# PowerSupply.net
KiCad netlist of a schematic drawn in Altium Designer
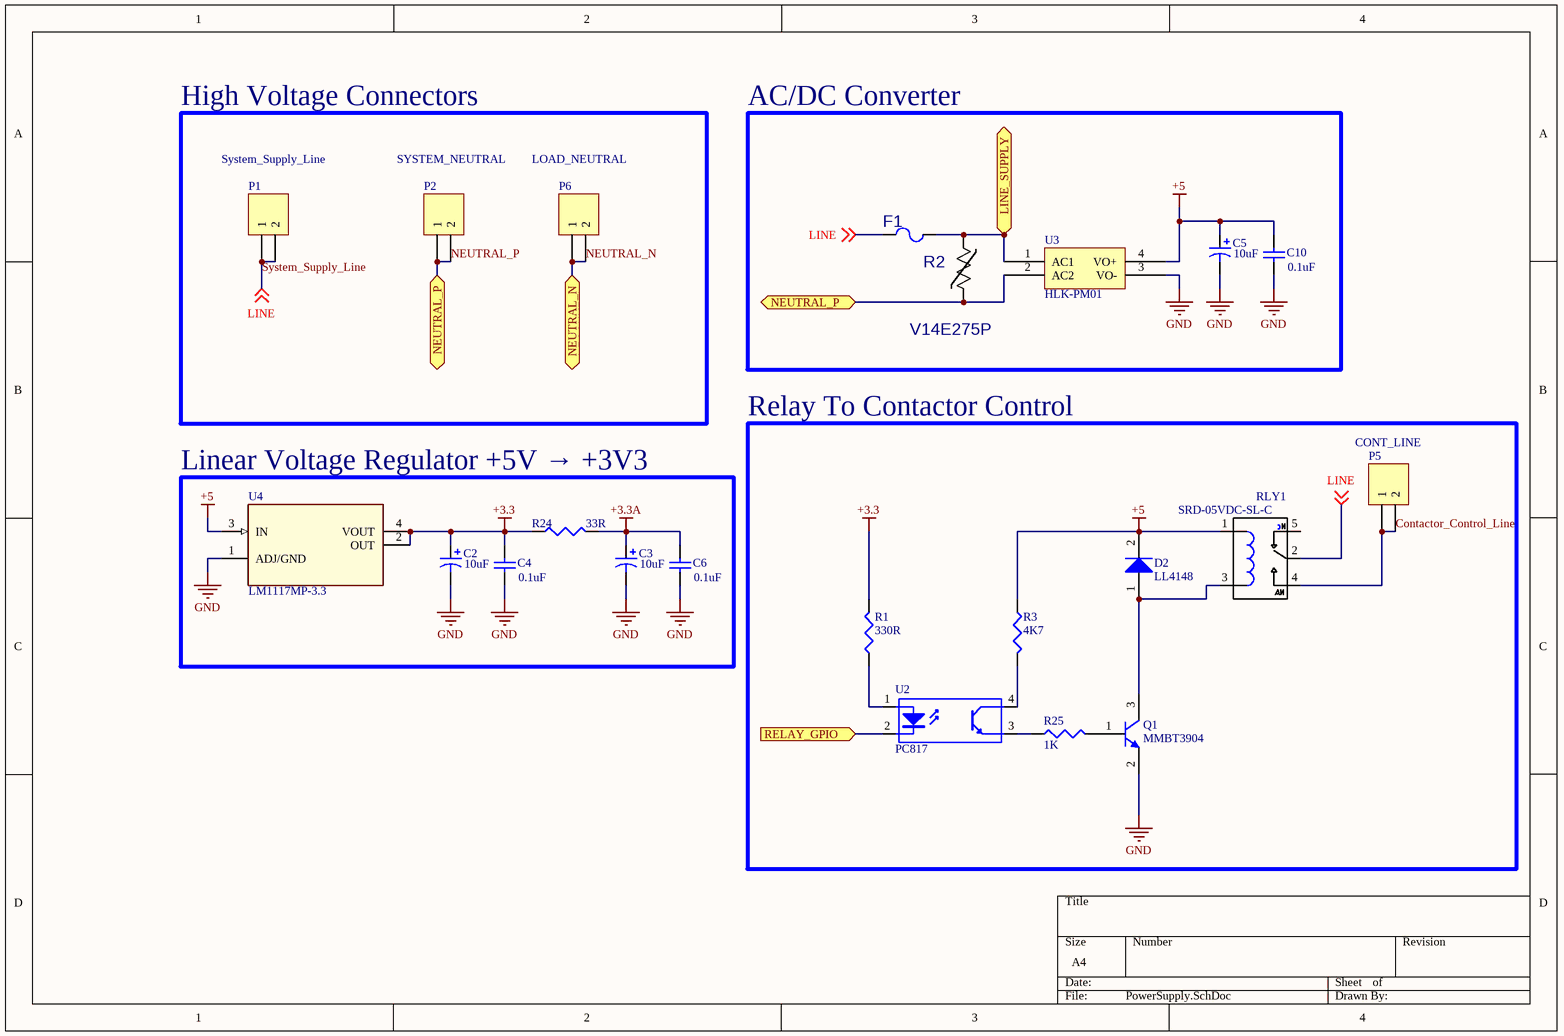
[diagram p0: PowerSupply.SchDoc]

(export (version "E")
  (design (tool "Eeschema 10.0.6"))
  (components
    (comp (ref "C2")
      (value "10uF")
      (footprint "EEE-1VA100WR")
      (description "Polarized Capacitor (Radial)")
      (fields (field (name "Comment") "Cap Pol1") (field (name "PUBLISHER") "Altium Limited"))
      (libsource (lib "Miscellaneous Devices") (part "Cap Pol1"))
    )
    (comp (ref "C3")
      (value "10uF")
      (footprint "EEE-1VA100WR")
      (description "Polarized Capacitor (Radial)")
      (fields (field (name "Comment") "Cap Pol1") (field (name "PUBLISHER") "Altium Limited"))
      (libsource (lib "Miscellaneous Devices") (part "Cap Pol1"))
    )
    (comp (ref "C4")
      (value "0.1uF")
      (footprint "C0603")
      (description "Capacitor (Semiconductor SIM Model)")
      (fields (field (name "Comment") "MUDAR FOOTPRINT") (field (name "PUBLISHER") "Altium Limited"))
      (libsource (lib "Miscellaneous Devices") (part "Cap Semi"))
    )
    (comp (ref "C5")
      (value "10uF")
      (footprint "EEE-1VA100WR")
      (description "Polarized Capacitor (Radial)")
      (fields (field (name "Comment") "Cap Pol1") (field (name "PUBLISHER") "Altium Limited"))
      (libsource (lib "Miscellaneous Devices") (part "Cap Pol1"))
    )
    (comp (ref "C6")
      (value "0.1uF")
      (footprint "C0603")
      (description "Capacitor (Semiconductor SIM Model)")
      (fields (field (name "Comment") "MUDAR FOOTPRINT") (field (name "PUBLISHER") "Altium Limited"))
      (libsource (lib "Miscellaneous Devices") (part "Cap Semi"))
    )
    (comp (ref "C10")
      (value "0.1uF")
      (footprint "C0603")
      (description "Capacitor (Semiconductor SIM Model)")
      (fields (field (name "Comment") "MUDAR FOOTPRINT") (field (name "PUBLISHER") "Altium Limited"))
      (libsource (lib "Miscellaneous Devices") (part "Cap Semi"))
    )
    (comp (ref "D2")
      (value "LL4148")
      (footprint "LL4148")
      (description "Default Diode")
      (fields (field (name "PUBLISHER") "Altium Limited"))
      (libsource (lib "Miscellaneous Devices") (part "Diode"))
    )
    (comp (ref "F1")
      (value "RSTA 1 AMMO")
      (footprint "RSTA")
      (libsource (lib "PowerMonitoring") (part "RSTA 1 AMMO"))
    )
    (comp (ref "P1")
      (value "System_Supply_Line")
      (footprint "1993763")
      (description "Header, 2-Pin")
      (fields (field (name "PUBLISHER") "Altium Limited"))
      (libsource (lib "Miscellaneous Connectors") (part "Header 2"))
    )
    (comp (ref "P2")
      (value "SYSTEM_NEUTRAL")
      (footprint "1993763")
      (description "Header, 2-Pin")
      (fields (field (name "PUBLISHER") "Altium Limited"))
      (libsource (lib "Miscellaneous Connectors") (part "Header 2"))
    )
    (comp (ref "P5")
      (value "CONT_LINE")
      (footprint "1993763")
      (description "Header, 2-Pin")
      (fields (field (name "PUBLISHER") "Altium Limited"))
      (libsource (lib "Miscellaneous Connectors") (part "Header 2"))
    )
    (comp (ref "P6")
      (value "LOAD_NEUTRAL")
      (footprint "1993763")
      (description "Header, 2-Pin")
      (fields (field (name "PUBLISHER") "Altium Limited"))
      (libsource (lib "Miscellaneous Connectors") (part "Header 2"))
    )
    (comp (ref "Q1")
      (value "MMBT3904")
      (footprint "SOT-233")
      (description "NPN Bipolar Transistor")
      (fields (field (name "PUBLISHER") "Altium Limited"))
      (libsource (lib "Miscellaneous Devices") (part "NPN"))
    )
    (comp (ref "R1")
      (value "330R")
      (footprint "R0603")
      (description "Resistor")
      (fields (field (name "Comment") "Res3") (field (name "PUBLISHER") "Altium Limited"))
      (libsource (lib "Miscellaneous Devices") (part "Res3"))
    )
    (comp (ref "R2")
      (value "V14E275P")
      (footprint "VARISTOR")
      (fields (field (name "MANUFACTURER_PART_NUMBER") "ERZ-V14D431"))
      (libsource (lib "PowerMonitoring") (part "ERZ-V14D431"))
    )
    (comp (ref "R3")
      (value "4K7")
      (footprint "R0603")
      (description "Resistor")
      (fields (field (name "Comment") "Res3") (field (name "PUBLISHER") "Altium Limited"))
      (libsource (lib "Miscellaneous Devices") (part "Res3"))
    )
    (comp (ref "R24")
      (value "33R")
      (footprint "R0603")
      (description "Resistor")
      (fields (field (name "Comment") "Res3") (field (name "PUBLISHER") "Altium Limited"))
      (libsource (lib "Miscellaneous Devices") (part "Res3"))
    )
    (comp (ref "R25")
      (value "1K")
      (footprint "R0603")
      (description "Resistor")
      (fields (field (name "Comment") "Res3") (field (name "PUBLISHER") "Altium Limited"))
      (libsource (lib "Miscellaneous Devices") (part "Res3"))
    )
    (comp (ref "RLY1")
      (value "SRD-05VDC-SL-C")
      (footprint "srd-05vdc")
      (fields (field (name "MF") "MCM Electronics"))
      (libsource (lib "PowerMonitoring") (part "SRD-05VDC-SL-C"))
    )
    (comp (ref "U2")
      (value "PC817")
      (footprint "SOT254P975X400-4N")
      (description "4-Pin Phototransistor Optocoupler")
      (fields (field (name "PUBLISHER") "Altium Limited"))
      (libsource (lib "Miscellaneous Devices") (part "Optoisolator1"))
    )
    (comp (ref "U3")
      (value "HLK-PM01")
      (footprint "HLK-PM01")
      (libsource (lib "PowerMonitoring") (part "HLK-PM01"))
    )
    (comp (ref "U4")
      (value "LM1117MP-3.3")
      (footprint "LM1117")
      (description "LDO Regulator Pos 3.3V 0.8A 4-Pin_3+Tab_ SOT-223 T/R")
      (fields (field (name "MF") "Texas Instruments"))
      (libsource (lib "PowerMonitoring") (part "LM1117MP-3.3"))
    )
  )
  (nets
    (net (code "1") (name "+3.3") (class "Default")
      (node (ref "C2") (pin "1") (pinfunction "1_1") (pintype "passive"))
      (node (ref "C4") (pin "2") (pinfunction "2_2") (pintype "passive"))
      (node (ref "R1") (pin "2") (pinfunction "2_2") (pintype "passive"))
      (node (ref "R24") (pin "1") (pinfunction "1_1") (pintype "passive"))
      (node (ref "U4") (pin "2") (pinfunction "OUT_2") (pintype "power_in"))
      (node (ref "U4") (pin "4") (pinfunction "VOUT_4") (pintype "power_in"))
    )
    (net (code "2") (name "+3.3A") (class "Default")
      (node (ref "C3") (pin "1") (pinfunction "1_1") (pintype "passive"))
      (node (ref "C6") (pin "2") (pinfunction "2_2") (pintype "passive"))
      (node (ref "R24") (pin "2") (pinfunction "2_2") (pintype "passive"))
    )
    (net (code "3") (name "+5") (class "Default")
      (node (ref "C10") (pin "2") (pinfunction "2_2") (pintype "passive"))
      (node (ref "C5") (pin "1") (pinfunction "1_1") (pintype "passive"))
      (node (ref "D2") (pin "2") (pinfunction "K_2") (pintype "passive"))
      (node (ref "R3") (pin "1") (pinfunction "1_1") (pintype "passive"))
      (node (ref "RLY1") (pin "1") (pinfunction "1_1") (pintype "passive"))
      (node (ref "U3") (pin "4") (pinfunction "VO+_4") (pintype "passive"))
      (node (ref "U4") (pin "3") (pinfunction "IN_3") (pintype "input"))
    )
    (net (code "4") (name "/Contactor_Control_Line") (class "Default")
      (node (ref "P5") (pin "1") (pinfunction "1_1") (pintype "passive"))
      (node (ref "P5") (pin "2") (pinfunction "2_2") (pintype "passive"))
      (node (ref "RLY1") (pin "4") (pinfunction "4_4") (pintype "passive"))
    )
    (net (code "5") (name "/LINE_SUPPLY") (class "Default")
      (node (ref "F1") (pin "2") (pinfunction "2_2") (pintype "passive"))
      (node (ref "R2") (pin "1") (pinfunction "1_1") (pintype "passive"))
      (node (ref "U3") (pin "1") (pinfunction "AC1_1") (pintype "passive"))
    )
    (net (code "6") (name "/NEUTRAL_N") (class "Default")
      (node (ref "P6") (pin "1") (pinfunction "1_1") (pintype "passive"))
      (node (ref "P6") (pin "2") (pinfunction "2_2") (pintype "passive"))
    )
    (net (code "7") (name "/NEUTRAL_P") (class "Default")
      (node (ref "P2") (pin "1") (pinfunction "1_1") (pintype "passive"))
      (node (ref "P2") (pin "2") (pinfunction "2_2") (pintype "passive"))
      (node (ref "R2") (pin "2") (pinfunction "2_2") (pintype "passive"))
      (node (ref "U3") (pin "2") (pinfunction "AC2_2") (pintype "passive"))
    )
    (net (code "8") (name "/RELAY_GPIO") (class "Default")
      (node (ref "U2") (pin "2") (pinfunction "K_2") (pintype "passive"))
    )
    (net (code "9") (name "GND") (class "Default")
      (node (ref "C10") (pin "1") (pinfunction "1_1") (pintype "passive"))
      (node (ref "C2") (pin "2") (pinfunction "2_2") (pintype "passive"))
      (node (ref "C3") (pin "2") (pinfunction "2_2") (pintype "passive"))
      (node (ref "C4") (pin "1") (pinfunction "1_1") (pintype "passive"))
      (node (ref "C5") (pin "2") (pinfunction "2_2") (pintype "passive"))
      (node (ref "C6") (pin "1") (pinfunction "1_1") (pintype "passive"))
      (node (ref "Q1") (pin "2") (pinfunction "E_2") (pintype "passive"))
      (node (ref "U3") (pin "3") (pinfunction "VO-_3") (pintype "passive"))
      (node (ref "U4") (pin "1") (pinfunction "ADJ/GND_1") (pintype "passive"))
    )
    (net (code "10") (name "LINE") (class "Default")
      (node (ref "F1") (pin "1") (pinfunction "1_1") (pintype "passive"))
      (node (ref "P1") (pin "1") (pinfunction "1_1") (pintype "passive"))
      (node (ref "P1") (pin "2") (pinfunction "2_2") (pintype "passive"))
      (node (ref "RLY1") (pin "2") (pinfunction "2_2") (pintype "passive"))
    )
    (net (code "11") (name "Net-(D2-A)") (class "Default")
      (node (ref "D2") (pin "1") (pinfunction "A_1") (pintype "passive"))
      (node (ref "Q1") (pin "3") (pinfunction "C_3") (pintype "passive"))
      (node (ref "RLY1") (pin "3") (pinfunction "3_3") (pintype "passive"))
    )
    (net (code "12") (name "Net-(Q1-B)") (class "Default")
      (node (ref "Q1") (pin "1") (pinfunction "B_1") (pintype "passive"))
      (node (ref "R25") (pin "2") (pinfunction "2_2") (pintype "passive"))
    )
    (net (code "13") (name "Net-(U2-A)") (class "Default")
      (node (ref "R1") (pin "1") (pinfunction "1_1") (pintype "passive"))
      (node (ref "U2") (pin "1") (pinfunction "A_1") (pintype "passive"))
    )
    (net (code "14") (name "Net-(U2-C)") (class "Default")
      (node (ref "R3") (pin "2") (pinfunction "2_2") (pintype "passive"))
      (node (ref "U2") (pin "4") (pinfunction "C_4") (pintype "passive"))
    )
    (net (code "15") (name "Net-(U2-E)") (class "Default")
      (node (ref "R25") (pin "1") (pinfunction "1_1") (pintype "passive"))
      (node (ref "U2") (pin "3") (pinfunction "E_3") (pintype "passive"))
    )
    (net (code "16") (name "unconnected-(RLY1-Pad5)") (class "Default")
      (node (ref "RLY1") (pin "5") (pinfunction "5_5") (pintype "passive"))
    )
  )
)
